# Sheet1.net
KiCad netlist of a schematic drawn in Altium Designer
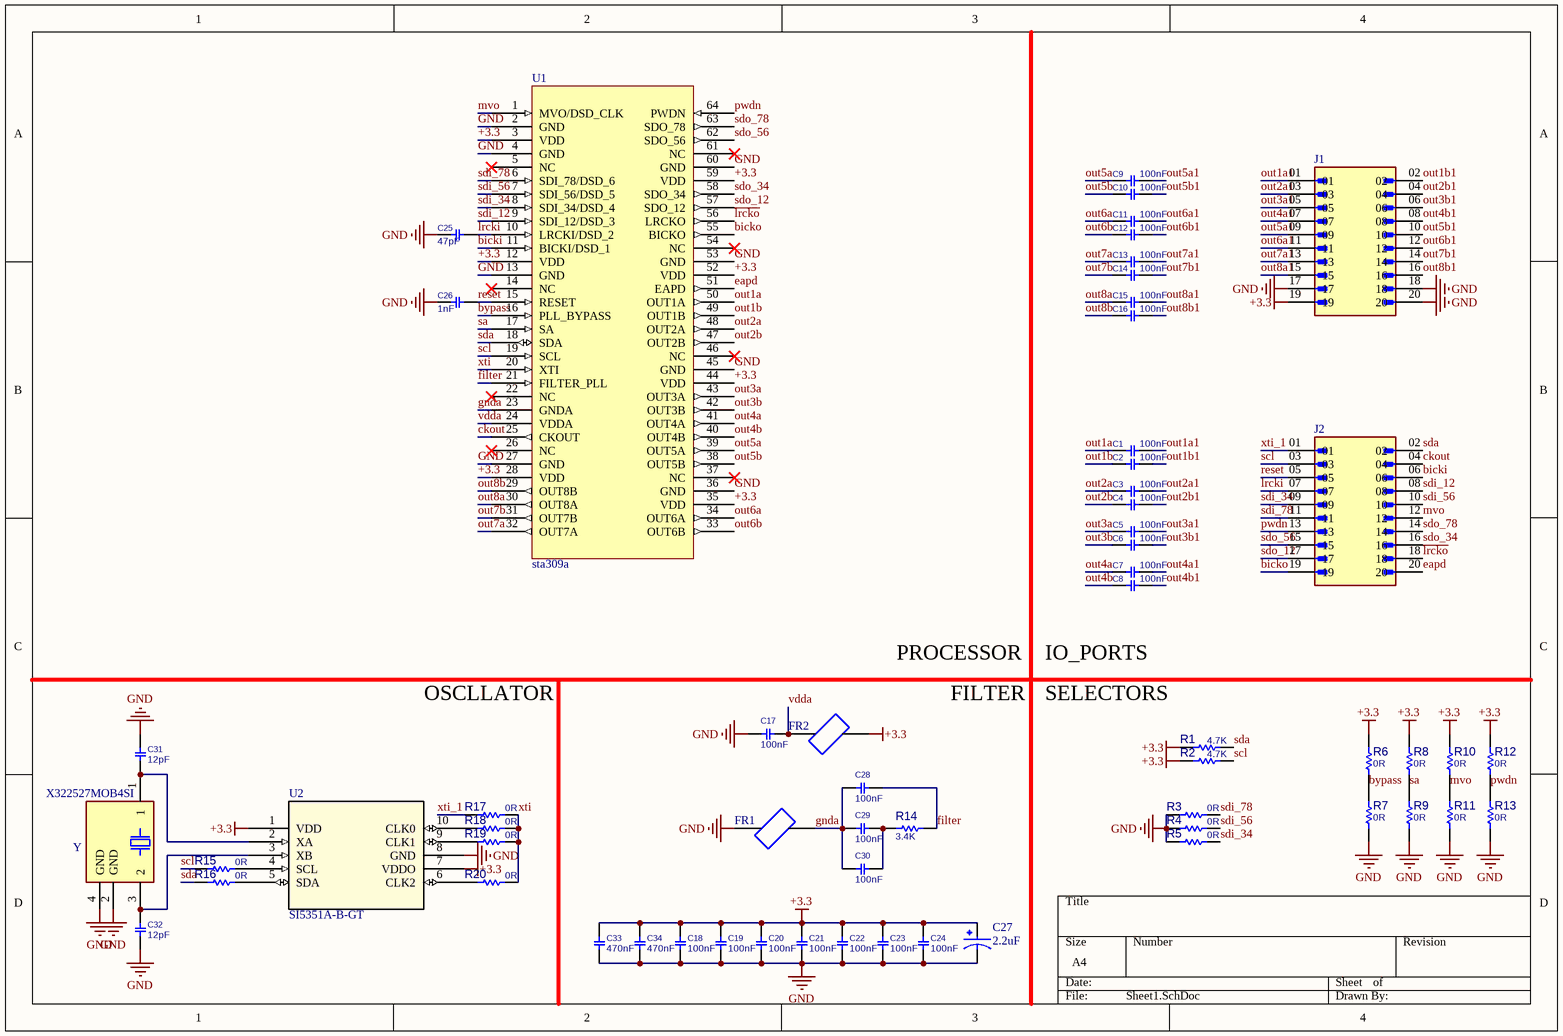
[diagram p0: Sheet1.SchDoc]

(export (version "E")
  (design (tool "Eeschema 10.0.6"))
  (components
    (comp (ref "C1")
      (value "100nF")
      (footprint "C0603")
      (description "CAP, MLCC")
      (fields (field (name "MANF_P#") "MANF_PART#"))
      (libsource (lib "receive") (part "CAP_SMD_MLCC_0603_1"))
    )
    (comp (ref "C2")
      (value "100nF")
      (footprint "C0603")
      (description "CAP, MLCC")
      (fields (field (name "MANF_P#") "MANF_PART#"))
      (libsource (lib "receive") (part "CAP_SMD_MLCC_0603_1"))
    )
    (comp (ref "C3")
      (value "100nF")
      (footprint "C0603")
      (description "CAP, MLCC")
      (fields (field (name "MANF_P#") "MANF_PART#"))
      (libsource (lib "receive") (part "CAP_SMD_MLCC_0603_1"))
    )
    (comp (ref "C4")
      (value "100nF")
      (footprint "C0603")
      (description "CAP, MLCC")
      (fields (field (name "MANF_P#") "MANF_PART#"))
      (libsource (lib "receive") (part "CAP_SMD_MLCC_0603_1"))
    )
    (comp (ref "C5")
      (value "100nF")
      (footprint "C0603")
      (description "CAP, MLCC")
      (fields (field (name "MANF_P#") "MANF_PART#"))
      (libsource (lib "receive") (part "CAP_SMD_MLCC_0603_1"))
    )
    (comp (ref "C6")
      (value "100nF")
      (footprint "C0603")
      (description "CAP, MLCC")
      (fields (field (name "MANF_P#") "MANF_PART#"))
      (libsource (lib "receive") (part "CAP_SMD_MLCC_0603_1"))
    )
    (comp (ref "C7")
      (value "100nF")
      (footprint "C0603")
      (description "CAP, MLCC")
      (fields (field (name "MANF_P#") "MANF_PART#"))
      (libsource (lib "receive") (part "CAP_SMD_MLCC_0603_1"))
    )
    (comp (ref "C8")
      (value "100nF")
      (footprint "C0603")
      (description "CAP, MLCC")
      (fields (field (name "MANF_P#") "MANF_PART#"))
      (libsource (lib "receive") (part "CAP_SMD_MLCC_0603_1"))
    )
    (comp (ref "C9")
      (value "100nF")
      (footprint "C0603")
      (description "CAP, MLCC")
      (fields (field (name "MANF_P#") "MANF_PART#"))
      (libsource (lib "receive") (part "CAP_SMD_MLCC_0603_1"))
    )
    (comp (ref "C10")
      (value "100nF")
      (footprint "C0603")
      (description "CAP, MLCC")
      (fields (field (name "MANF_P#") "MANF_PART#"))
      (libsource (lib "receive") (part "CAP_SMD_MLCC_0603_1"))
    )
    (comp (ref "C11")
      (value "100nF")
      (footprint "C0603")
      (description "CAP, MLCC")
      (fields (field (name "MANF_P#") "MANF_PART#"))
      (libsource (lib "receive") (part "CAP_SMD_MLCC_0603_1"))
    )
    (comp (ref "C12")
      (value "100nF")
      (footprint "C0603")
      (description "CAP, MLCC")
      (fields (field (name "MANF_P#") "MANF_PART#"))
      (libsource (lib "receive") (part "CAP_SMD_MLCC_0603_1"))
    )
    (comp (ref "C13")
      (value "100nF")
      (footprint "C0603")
      (description "CAP, MLCC")
      (fields (field (name "MANF_P#") "MANF_PART#"))
      (libsource (lib "receive") (part "CAP_SMD_MLCC_0603_1"))
    )
    (comp (ref "C14")
      (value "100nF")
      (footprint "C0603")
      (description "CAP, MLCC")
      (fields (field (name "MANF_P#") "MANF_PART#"))
      (libsource (lib "receive") (part "CAP_SMD_MLCC_0603_1"))
    )
    (comp (ref "C15")
      (value "100nF")
      (footprint "C0603")
      (description "CAP, MLCC")
      (fields (field (name "MANF_P#") "MANF_PART#"))
      (libsource (lib "receive") (part "CAP_SMD_MLCC_0603_1"))
    )
    (comp (ref "C16")
      (value "100nF")
      (footprint "C0603")
      (description "CAP, MLCC")
      (fields (field (name "MANF_P#") "MANF_PART#"))
      (libsource (lib "receive") (part "CAP_SMD_MLCC_0603_1"))
    )
    (comp (ref "C17")
      (value "100nF")
      (footprint "C0603")
      (description "CAP, MLCC")
      (fields (field (name "MANF_P#") "MANF_PART#"))
      (libsource (lib "receive") (part "CAP_SMD_MLCC_0603_1"))
    )
    (comp (ref "C18")
      (value "100nF")
      (footprint "C0603")
      (description "CAP, MLCC")
      (fields (field (name "MANF_P#") "MANF_PART#"))
      (libsource (lib "receive") (part "CAP_SMD_MLCC_0603_1"))
    )
    (comp (ref "C19")
      (value "100nF")
      (footprint "C0603")
      (description "CAP, MLCC")
      (fields (field (name "MANF_P#") "MANF_PART#"))
      (libsource (lib "receive") (part "CAP_SMD_MLCC_0603_1"))
    )
    (comp (ref "C20")
      (value "100nF")
      (footprint "C0603")
      (description "CAP, MLCC")
      (fields (field (name "MANF_P#") "MANF_PART#"))
      (libsource (lib "receive") (part "CAP_SMD_MLCC_0603_1"))
    )
    (comp (ref "C21")
      (value "100nF")
      (footprint "C0603")
      (description "CAP, MLCC")
      (fields (field (name "MANF_P#") "MANF_PART#"))
      (libsource (lib "receive") (part "CAP_SMD_MLCC_0603_1"))
    )
    (comp (ref "C22")
      (value "100nF")
      (footprint "C0603")
      (description "CAP, MLCC")
      (fields (field (name "MANF_P#") "MANF_PART#"))
      (libsource (lib "receive") (part "CAP_SMD_MLCC_0603_1"))
    )
    (comp (ref "C23")
      (value "100nF")
      (footprint "C0603")
      (description "CAP, MLCC")
      (fields (field (name "MANF_P#") "MANF_PART#"))
      (libsource (lib "receive") (part "CAP_SMD_MLCC_0603_1"))
    )
    (comp (ref "C24")
      (value "100nF")
      (footprint "C0603")
      (description "CAP, MLCC")
      (fields (field (name "MANF_P#") "MANF_PART#"))
      (libsource (lib "receive") (part "CAP_SMD_MLCC_0603_1"))
    )
    (comp (ref "C25")
      (value "47pF")
      (footprint "C0603")
      (description "CAP, MLCC")
      (fields (field (name "MANF_P#") "MANF_PART#"))
      (libsource (lib "receive") (part "CAP_SMD_MLCC_0603_1"))
    )
    (comp (ref "C26")
      (value "1nF")
      (footprint "C0603")
      (description "CAP, MLCC")
      (fields (field (name "MANF_P#") "MANF_PART#"))
      (libsource (lib "receive") (part "CAP_SMD_MLCC_0603_1"))
    )
    (comp (ref "C27")
      (value "2.2uF")
      (footprint "CAPMP3216X180N")
      (description "Capacitors Tantalum PCB 4.7uF SMD Tol 10% 10 VDC Case Size 3216 T491 Series ¦ KEMET T491A475K010AT")
      (fields (field (name "MF") "KEMET") (field (name "MP") "T491A475K010AT"))
      (libsource (lib "T491A475K010AT") (part "T491A475K010AT"))
    )
    (comp (ref "C28")
      (value "100nF")
      (footprint "C0603")
      (description "CAP, MLCC")
      (fields (field (name "MANF_P#") "MANF_PART#"))
      (libsource (lib "receive") (part "CAP_SMD_MLCC_0603_1"))
    )
    (comp (ref "C29")
      (value "100nF")
      (footprint "C0603")
      (description "CAP, MLCC")
      (fields (field (name "MANF_P#") "MANF_PART#"))
      (libsource (lib "receive") (part "CAP_SMD_MLCC_0603_1"))
    )
    (comp (ref "C30")
      (value "100nF")
      (footprint "C0603")
      (description "CAP, MLCC")
      (fields (field (name "MANF_P#") "MANF_PART#"))
      (libsource (lib "receive") (part "CAP_SMD_MLCC_0603_1"))
    )
    (comp (ref "C31")
      (value "12pF")
      (footprint "C0603")
      (description "CAP, MLCC")
      (fields (field (name "MANF_P#") "MANF_PART#"))
      (libsource (lib "receive") (part "CAP_SMD_MLCC_0603_1"))
    )
    (comp (ref "C32")
      (value "12pF")
      (footprint "C0603")
      (description "CAP, MLCC")
      (fields (field (name "MANF_P#") "MANF_PART#"))
      (libsource (lib "receive") (part "CAP_SMD_MLCC_0603_1"))
    )
    (comp (ref "C33")
      (value "470nF")
      (footprint "C0603")
      (description "CAP, MLCC")
      (fields (field (name "MANF_P#") "MANF_PART#"))
      (libsource (lib "receive") (part "CAP_SMD_MLCC_0603_1"))
    )
    (comp (ref "C34")
      (value "470nF")
      (footprint "C0603")
      (description "CAP, MLCC")
      (fields (field (name "MANF_P#") "MANF_PART#"))
      (libsource (lib "receive") (part "CAP_SMD_MLCC_0603_1"))
    )
    (comp (ref "FR1")
      (value "MI0805K400R-10")
      (footprint "FB_MI0805K400R-10")
      (description "40 Ohms @ 100MHz 1 Power Line Ferrite Bead 0805 (2012 Metric) 1.5A 50mOhm")
      (fields (field (name "MF") "Laird-Signal Integrity Products"))
      (libsource (lib "MI0805K400R-10") (part "MI0805K400R-10"))
    )
    (comp (ref "FR2")
      (value "MI0805K400R-10")
      (footprint "FB_MI0805K400R-10")
      (description "40 Ohms @ 100MHz 1 Power Line Ferrite Bead 0805 (2012 Metric) 1.5A 50mOhm")
      (fields (field (name "MF") "Laird-Signal Integrity Products"))
      (libsource (lib "MI0805K400R-10") (part "MI0805K400R-10"))
    )
    (comp (ref "J1")
      (value "VMHD-2x10-150-095-030")
      (footprint "VALCON_VMHD-2x10-150-095-030")
      (libsource (lib "VMHD-2x10-150-095-030") (part "VMHD-2x10-150-095-030"))
    )
    (comp (ref "J2")
      (value "VMHD-2x10-150-095-030")
      (footprint "VALCON_VMHD-2x10-150-095-030")
      (libsource (lib "VMHD-2x10-150-095-030") (part "VMHD-2x10-150-095-030"))
    )
    (comp (ref "R1")
      (value "4.7K")
      (footprint "R0603")
      (description "RESISTOR, SMD")
      (libsource (lib "receive") (part "RES_SMD_0603_1"))
    )
    (comp (ref "R2")
      (value "4.7K")
      (footprint "R0603")
      (description "RESISTOR, SMD")
      (libsource (lib "receive") (part "RES_SMD_0603_1"))
    )
    (comp (ref "R3")
      (value "0R")
      (footprint "R0603")
      (description "RESISTOR, SMD")
      (libsource (lib "receive") (part "RES_SMD_0603_1"))
    )
    (comp (ref "R4")
      (value "0R")
      (footprint "R0603")
      (description "RESISTOR, SMD")
      (libsource (lib "receive") (part "RES_SMD_0603_1"))
    )
    (comp (ref "R5")
      (value "0R")
      (footprint "R0603")
      (description "RESISTOR, SMD")
      (libsource (lib "receive") (part "RES_SMD_0603_1"))
    )
    (comp (ref "R6")
      (value "0R")
      (footprint "R0603")
      (description "RESISTOR, SMD")
      (libsource (lib "receive") (part "RES_SMD_0603_1"))
    )
    (comp (ref "R7")
      (value "0R")
      (footprint "R0603")
      (description "RESISTOR, SMD")
      (libsource (lib "receive") (part "RES_SMD_0603_1"))
    )
    (comp (ref "R8")
      (value "0R")
      (footprint "R0603")
      (description "RESISTOR, SMD")
      (libsource (lib "receive") (part "RES_SMD_0603_1"))
    )
    (comp (ref "R9")
      (value "0R")
      (footprint "R0603")
      (description "RESISTOR, SMD")
      (libsource (lib "receive") (part "RES_SMD_0603_1"))
    )
    (comp (ref "R10")
      (value "0R")
      (footprint "R0603")
      (description "RESISTOR, SMD")
      (libsource (lib "receive") (part "RES_SMD_0603_1"))
    )
    (comp (ref "R11")
      (value "0R")
      (footprint "R0603")
      (description "RESISTOR, SMD")
      (libsource (lib "receive") (part "RES_SMD_0603_1"))
    )
    (comp (ref "R12")
      (value "0R")
      (footprint "R0603")
      (description "RESISTOR, SMD")
      (libsource (lib "receive") (part "RES_SMD_0603_1"))
    )
    (comp (ref "R13")
      (value "0R")
      (footprint "R0603")
      (description "RESISTOR, SMD")
      (libsource (lib "receive") (part "RES_SMD_0603_1"))
    )
    (comp (ref "R14")
      (value "3.4K")
      (footprint "R0603")
      (description "RESISTOR, SMD")
      (libsource (lib "receive") (part "RES_SMD_0603_1"))
    )
    (comp (ref "R15")
      (value "0R")
      (footprint "R0603")
      (description "RESISTOR, SMD")
      (libsource (lib "receive") (part "RES_SMD_0603_1"))
    )
    (comp (ref "R16")
      (value "0R")
      (footprint "R0603")
      (description "RESISTOR, SMD")
      (libsource (lib "receive") (part "RES_SMD_0603_1"))
    )
    (comp (ref "R17")
      (value "0R")
      (footprint "R0603")
      (description "RESISTOR, SMD")
      (libsource (lib "receive") (part "RES_SMD_0603_1"))
    )
    (comp (ref "R18")
      (value "0R")
      (footprint "R0603")
      (description "RESISTOR, SMD")
      (libsource (lib "receive") (part "RES_SMD_0603_1"))
    )
    (comp (ref "R19")
      (value "0R")
      (footprint "R0603")
      (description "RESISTOR, SMD")
      (libsource (lib "receive") (part "RES_SMD_0603_1"))
    )
    (comp (ref "R20")
      (value "0R")
      (footprint "R0603")
      (description "RESISTOR, SMD")
      (libsource (lib "receive") (part "RES_SMD_0603_1"))
    )
    (comp (ref "U1")
      (value "sta309a")
      (footprint "QFP50P1200X1200X120-64N")
      (libsource (lib "sta309a") (part "sta309a"))
    )
    (comp (ref "U2")
      (value "SI5351A-B-GT")
      (footprint "10MSOP_3X3_SIL")
      (description "No Description Available")
      (fields (field (name "COPYRIGHT") "Copyright (C) 2025 Ultra Librarian. All rights reserved."))
      (libsource (lib "SI5351A-B-GT") (part "SI5351A-B-GT"))
    )
    (comp (ref "Y")
      (value "X322527MOB4SI")
      (footprint "XTAL_TSX-3225_16.0000MF18X-AC3")
      (description "16 MHz Â±10ppm Crystal 18pF 60 Ohms 4-SMD, No Lead")
      (fields (field (name "MF") "EPSON") (field (name "MP") "TSX-3225 16.0000MF18X-AC3"))
      (libsource (lib "TSX-3225_16.0000MF18X-AC3") (part "TSX-3225_16.0000MF18X-AC3"))
    )
  )
  (nets
    (net (code "1") (name "+3.3") (class "Default")
      (node (ref "C18") (pin "2") (pinfunction "2_2") (pintype "passive"))
      (node (ref "C19") (pin "2") (pinfunction "2_2") (pintype "passive"))
      (node (ref "C20") (pin "2") (pinfunction "2_2") (pintype "passive"))
      (node (ref "C21") (pin "2") (pinfunction "2_2") (pintype "passive"))
      (node (ref "C22") (pin "2") (pinfunction "2_2") (pintype "passive"))
      (node (ref "C23") (pin "2") (pinfunction "2_2") (pintype "passive"))
      (node (ref "C24") (pin "2") (pinfunction "2_2") (pintype "passive"))
      (node (ref "C27") (pin "1") (pinfunction "1_1") (pintype "passive"))
      (node (ref "C33") (pin "2") (pinfunction "2_2") (pintype "passive"))
      (node (ref "C34") (pin "2") (pinfunction "2_2") (pintype "passive"))
      (node (ref "FR2") (pin "1") (pinfunction "1_1") (pintype "passive"))
      (node (ref "J1") (pin "19") (pinfunction "19_19") (pintype "passive"))
      (node (ref "R1") (pin "1") (pinfunction "1_1") (pintype "passive"))
      (node (ref "R10") (pin "1") (pinfunction "1_1") (pintype "passive"))
      (node (ref "R12") (pin "1") (pinfunction "1_1") (pintype "passive"))
      (node (ref "R2") (pin "1") (pinfunction "1_1") (pintype "passive"))
      (node (ref "R6") (pin "1") (pinfunction "1_1") (pintype "passive"))
      (node (ref "R8") (pin "1") (pinfunction "1_1") (pintype "passive"))
      (node (ref "U1") (pin "12") (pinfunction "VDD_12") (pintype "power_in"))
      (node (ref "U1") (pin "28") (pinfunction "VDD_28") (pintype "power_in"))
      (node (ref "U1") (pin "3") (pinfunction "VDD_3") (pintype "power_in"))
      (node (ref "U1") (pin "35") (pinfunction "VDD_35") (pintype "power_in"))
      (node (ref "U1") (pin "44") (pinfunction "VDD_44") (pintype "power_in"))
      (node (ref "U1") (pin "52") (pinfunction "VDD_52") (pintype "power_in"))
      (node (ref "U1") (pin "59") (pinfunction "VDD_59") (pintype "power_in"))
      (node (ref "U2") (pin "1") (pinfunction "VDD_1") (pintype "power_in"))
      (node (ref "U2") (pin "7") (pinfunction "VDDO_7") (pintype "power_in"))
    )
    (net (code "2") (name "/bicki") (class "Default")
      (node (ref "J2") (pin "06") (pinfunction "06_06") (pintype "passive"))
      (node (ref "U1") (pin "11") (pinfunction "BICKI/DSD_1_11") (pintype "input"))
    )
    (net (code "3") (name "/bicko") (class "Default")
      (node (ref "J2") (pin "19") (pinfunction "19_19") (pintype "passive"))
      (node (ref "U1") (pin "55") (pinfunction "BICKO_55") (pintype "output"))
    )
    (net (code "4") (name "/bypass") (class "Default")
      (node (ref "R6") (pin "2") (pinfunction "2_2") (pintype "passive"))
      (node (ref "R7") (pin "2") (pinfunction "2_2") (pintype "passive"))
      (node (ref "U1") (pin "16") (pinfunction "PLL_BYPASS_16") (pintype "input"))
    )
    (net (code "5") (name "/ckout") (class "Default")
      (node (ref "J2") (pin "04") (pinfunction "04_04") (pintype "passive"))
      (node (ref "U1") (pin "25") (pinfunction "CKOUT_25") (pintype "output"))
    )
    (net (code "6") (name "/eapd") (class "Default")
      (node (ref "J2") (pin "20") (pinfunction "20_20") (pintype "passive"))
      (node (ref "U1") (pin "51") (pinfunction "EAPD_51") (pintype "output"))
    )
    (net (code "7") (name "/filter") (class "Default")
      (node (ref "C28") (pin "1") (pinfunction "1_1") (pintype "passive"))
      (node (ref "R14") (pin "2") (pinfunction "2_2") (pintype "passive"))
      (node (ref "U1") (pin "21") (pinfunction "FILTER_PLL_21") (pintype "input"))
    )
    (net (code "8") (name "/gnda") (class "Default")
      (node (ref "C28") (pin "2") (pinfunction "2_2") (pintype "passive"))
      (node (ref "C29") (pin "2") (pinfunction "2_2") (pintype "passive"))
      (node (ref "C30") (pin "2") (pinfunction "2_2") (pintype "passive"))
      (node (ref "FR1") (pin "2") (pinfunction "2_2") (pintype "passive"))
      (node (ref "U1") (pin "23") (pinfunction "GNDA_23") (pintype "power_in"))
    )
    (net (code "9") (name "/lrcki") (class "Default")
      (node (ref "C25") (pin "1") (pinfunction "1_1") (pintype "passive"))
      (node (ref "J2") (pin "07") (pinfunction "07_07") (pintype "passive"))
      (node (ref "U1") (pin "10") (pinfunction "LRCKI/DSD_2_10") (pintype "input"))
    )
    (net (code "10") (name "/lrcko") (class "Default")
      (node (ref "J2") (pin "18") (pinfunction "18_18") (pintype "passive"))
      (node (ref "U1") (pin "56") (pinfunction "LRCKO_56") (pintype "output"))
    )
    (net (code "11") (name "/mvo") (class "Default")
      (node (ref "J2") (pin "12") (pinfunction "12_12") (pintype "passive"))
      (node (ref "R10") (pin "2") (pinfunction "2_2") (pintype "passive"))
      (node (ref "R11") (pin "2") (pinfunction "2_2") (pintype "passive"))
      (node (ref "U1") (pin "1") (pinfunction "MVO/DSD_CLK_1") (pintype "input"))
    )
    (net (code "12") (name "/out1a") (class "Default")
      (node (ref "C1") (pin "1") (pinfunction "1_1") (pintype "passive"))
      (node (ref "U1") (pin "50") (pinfunction "OUT1A_50") (pintype "output"))
    )
    (net (code "13") (name "/out1a1") (class "Default")
      (node (ref "C1") (pin "2") (pinfunction "2_2") (pintype "passive"))
      (node (ref "J1") (pin "01") (pinfunction "01_01") (pintype "passive"))
    )
    (net (code "14") (name "/out1b") (class "Default")
      (node (ref "C2") (pin "1") (pinfunction "1_1") (pintype "passive"))
      (node (ref "U1") (pin "49") (pinfunction "OUT1B_49") (pintype "output"))
    )
    (net (code "15") (name "/out1b1") (class "Default")
      (node (ref "C2") (pin "2") (pinfunction "2_2") (pintype "passive"))
      (node (ref "J1") (pin "02") (pinfunction "02_02") (pintype "passive"))
    )
    (net (code "16") (name "/out2a") (class "Default")
      (node (ref "C3") (pin "1") (pinfunction "1_1") (pintype "passive"))
      (node (ref "U1") (pin "48") (pinfunction "OUT2A_48") (pintype "output"))
    )
    (net (code "17") (name "/out2a1") (class "Default")
      (node (ref "C3") (pin "2") (pinfunction "2_2") (pintype "passive"))
      (node (ref "J1") (pin "03") (pinfunction "03_03") (pintype "passive"))
    )
    (net (code "18") (name "/out2b") (class "Default")
      (node (ref "C4") (pin "1") (pinfunction "1_1") (pintype "passive"))
      (node (ref "U1") (pin "47") (pinfunction "OUT2B_47") (pintype "output"))
    )
    (net (code "19") (name "/out2b1") (class "Default")
      (node (ref "C4") (pin "2") (pinfunction "2_2") (pintype "passive"))
      (node (ref "J1") (pin "04") (pinfunction "04_04") (pintype "passive"))
    )
    (net (code "20") (name "/out3a") (class "Default")
      (node (ref "C5") (pin "1") (pinfunction "1_1") (pintype "passive"))
      (node (ref "U1") (pin "43") (pinfunction "OUT3A_43") (pintype "output"))
    )
    (net (code "21") (name "/out3a1") (class "Default")
      (node (ref "C5") (pin "2") (pinfunction "2_2") (pintype "passive"))
      (node (ref "J1") (pin "05") (pinfunction "05_05") (pintype "passive"))
    )
    (net (code "22") (name "/out3b") (class "Default")
      (node (ref "C6") (pin "1") (pinfunction "1_1") (pintype "passive"))
      (node (ref "U1") (pin "42") (pinfunction "OUT3B_42") (pintype "output"))
    )
    (net (code "23") (name "/out3b1") (class "Default")
      (node (ref "C6") (pin "2") (pinfunction "2_2") (pintype "passive"))
      (node (ref "J1") (pin "06") (pinfunction "06_06") (pintype "passive"))
    )
    (net (code "24") (name "/out4a") (class "Default")
      (node (ref "C7") (pin "1") (pinfunction "1_1") (pintype "passive"))
      (node (ref "U1") (pin "41") (pinfunction "OUT4A_41") (pintype "output"))
    )
    (net (code "25") (name "/out4a1") (class "Default")
      (node (ref "C7") (pin "2") (pinfunction "2_2") (pintype "passive"))
      (node (ref "J1") (pin "07") (pinfunction "07_07") (pintype "passive"))
    )
    (net (code "26") (name "/out4b") (class "Default")
      (node (ref "C8") (pin "1") (pinfunction "1_1") (pintype "passive"))
      (node (ref "U1") (pin "40") (pinfunction "OUT4B_40") (pintype "output"))
    )
    (net (code "27") (name "/out4b1") (class "Default")
      (node (ref "C8") (pin "2") (pinfunction "2_2") (pintype "passive"))
      (node (ref "J1") (pin "08") (pinfunction "08_08") (pintype "passive"))
    )
    (net (code "28") (name "/out5a") (class "Default")
      (node (ref "C9") (pin "1") (pinfunction "1_1") (pintype "passive"))
      (node (ref "U1") (pin "39") (pinfunction "OUT5A_39") (pintype "output"))
    )
    (net (code "29") (name "/out5a1") (class "Default")
      (node (ref "C9") (pin "2") (pinfunction "2_2") (pintype "passive"))
      (node (ref "J1") (pin "09") (pinfunction "09_09") (pintype "passive"))
    )
    (net (code "30") (name "/out5b") (class "Default")
      (node (ref "C10") (pin "1") (pinfunction "1_1") (pintype "passive"))
      (node (ref "U1") (pin "38") (pinfunction "OUT5B_38") (pintype "output"))
    )
    (net (code "31") (name "/out5b1") (class "Default")
      (node (ref "C10") (pin "2") (pinfunction "2_2") (pintype "passive"))
      (node (ref "J1") (pin "10") (pinfunction "10_10") (pintype "passive"))
    )
    (net (code "32") (name "/out6a") (class "Default")
      (node (ref "C11") (pin "1") (pinfunction "1_1") (pintype "passive"))
      (node (ref "U1") (pin "34") (pinfunction "OUT6A_34") (pintype "output"))
    )
    (net (code "33") (name "/out6a1") (class "Default")
      (node (ref "C11") (pin "2") (pinfunction "2_2") (pintype "passive"))
      (node (ref "J1") (pin "11") (pinfunction "11_11") (pintype "passive"))
    )
    (net (code "34") (name "/out6b") (class "Default")
      (node (ref "C12") (pin "1") (pinfunction "1_1") (pintype "passive"))
      (node (ref "U1") (pin "33") (pinfunction "OUT6B_33") (pintype "output"))
    )
    (net (code "35") (name "/out6b1") (class "Default")
      (node (ref "C12") (pin "2") (pinfunction "2_2") (pintype "passive"))
      (node (ref "J1") (pin "12") (pinfunction "12_12") (pintype "passive"))
    )
    (net (code "36") (name "/out7a") (class "Default")
      (node (ref "C13") (pin "1") (pinfunction "1_1") (pintype "passive"))
      (node (ref "U1") (pin "32") (pinfunction "OUT7A_32") (pintype "output"))
    )
    (net (code "37") (name "/out7a1") (class "Default")
      (node (ref "C13") (pin "2") (pinfunction "2_2") (pintype "passive"))
      (node (ref "J1") (pin "13") (pinfunction "13_13") (pintype "passive"))
    )
    (net (code "38") (name "/out7b") (class "Default")
      (node (ref "C14") (pin "1") (pinfunction "1_1") (pintype "passive"))
      (node (ref "U1") (pin "31") (pinfunction "OUT7B_31") (pintype "output"))
    )
    (net (code "39") (name "/out7b1") (class "Default")
      (node (ref "C14") (pin "2") (pinfunction "2_2") (pintype "passive"))
      (node (ref "J1") (pin "14") (pinfunction "14_14") (pintype "passive"))
    )
    (net (code "40") (name "/out8a") (class "Default")
      (node (ref "C15") (pin "1") (pinfunction "1_1") (pintype "passive"))
      (node (ref "U1") (pin "30") (pinfunction "OUT8A_30") (pintype "output"))
    )
    (net (code "41") (name "/out8a1") (class "Default")
      (node (ref "C15") (pin "2") (pinfunction "2_2") (pintype "passive"))
      (node (ref "J1") (pin "15") (pinfunction "15_15") (pintype "passive"))
    )
    (net (code "42") (name "/out8b") (class "Default")
      (node (ref "C16") (pin "1") (pinfunction "1_1") (pintype "passive"))
      (node (ref "U1") (pin "29") (pinfunction "OUT8B_29") (pintype "output"))
    )
    (net (code "43") (name "/out8b1") (class "Default")
      (node (ref "C16") (pin "2") (pinfunction "2_2") (pintype "passive"))
      (node (ref "J1") (pin "16") (pinfunction "16_16") (pintype "passive"))
    )
    (net (code "44") (name "/pwdn") (class "Default")
      (node (ref "J2") (pin "13") (pinfunction "13_13") (pintype "passive"))
      (node (ref "R12") (pin "2") (pinfunction "2_2") (pintype "passive"))
      (node (ref "R13") (pin "2") (pinfunction "2_2") (pintype "passive"))
      (node (ref "U1") (pin "64") (pinfunction "PWDN_64") (pintype "input"))
    )
    (net (code "45") (name "/reset") (class "Default")
      (node (ref "C26") (pin "1") (pinfunction "1_1") (pintype "passive"))
      (node (ref "J2") (pin "05") (pinfunction "05_05") (pintype "passive"))
      (node (ref "U1") (pin "15") (pinfunction "RESET_15") (pintype "input"))
    )
    (net (code "46") (name "/sa") (class "Default")
      (node (ref "R8") (pin "2") (pinfunction "2_2") (pintype "passive"))
      (node (ref "R9") (pin "2") (pinfunction "2_2") (pintype "passive"))
      (node (ref "U1") (pin "17") (pinfunction "SA_17") (pintype "input"))
    )
    (net (code "47") (name "/scl") (class "Default")
      (node (ref "J2") (pin "03") (pinfunction "03_03") (pintype "passive"))
      (node (ref "R15") (pin "1") (pinfunction "1_1") (pintype "passive"))
      (node (ref "R2") (pin "2") (pinfunction "2_2") (pintype "passive"))
      (node (ref "U1") (pin "19") (pinfunction "SCL_19") (pintype "input"))
    )
    (net (code "48") (name "/sda") (class "Default")
      (node (ref "J2") (pin "02") (pinfunction "02_02") (pintype "passive"))
      (node (ref "R1") (pin "2") (pinfunction "2_2") (pintype "passive"))
      (node (ref "R16") (pin "1") (pinfunction "1_1") (pintype "passive"))
      (node (ref "U1") (pin "18") (pinfunction "SDA_18") (pintype "bidirectional"))
    )
    (net (code "49") (name "/sdi_12") (class "Default")
      (node (ref "J2") (pin "08") (pinfunction "08_08") (pintype "passive"))
      (node (ref "U1") (pin "9") (pinfunction "SDI_12/DSD_3_9") (pintype "input"))
    )
    (net (code "50") (name "/sdi_34") (class "Default")
      (node (ref "J2") (pin "09") (pinfunction "09_09") (pintype "passive"))
      (node (ref "R5") (pin "2") (pinfunction "2_2") (pintype "passive"))
      (node (ref "U1") (pin "8") (pinfunction "SDI_34/DSD_4_8") (pintype "input"))
    )
    (net (code "51") (name "/sdi_56") (class "Default")
      (node (ref "J2") (pin "10") (pinfunction "10_10") (pintype "passive"))
      (node (ref "R4") (pin "2") (pinfunction "2_2") (pintype "passive"))
      (node (ref "U1") (pin "7") (pinfunction "SDI_56/DSD_5_7") (pintype "input"))
    )
    (net (code "52") (name "/sdi_78") (class "Default")
      (node (ref "J2") (pin "11") (pinfunction "11_11") (pintype "passive"))
      (node (ref "R3") (pin "2") (pinfunction "2_2") (pintype "passive"))
      (node (ref "U1") (pin "6") (pinfunction "SDI_78/DSD_6_6") (pintype "input"))
    )
    (net (code "53") (name "/sdo_12") (class "Default")
      (node (ref "J2") (pin "17") (pinfunction "17_17") (pintype "passive"))
      (node (ref "U1") (pin "57") (pinfunction "SDO_12_57") (pintype "output"))
    )
    (net (code "54") (name "/sdo_34") (class "Default")
      (node (ref "J2") (pin "16") (pinfunction "16_16") (pintype "passive"))
      (node (ref "U1") (pin "58") (pinfunction "SDO_34_58") (pintype "output"))
    )
    (net (code "55") (name "/sdo_56") (class "Default")
      (node (ref "J2") (pin "15") (pinfunction "15_15") (pintype "passive"))
      (node (ref "U1") (pin "62") (pinfunction "SDO_56_62") (pintype "output"))
    )
    (net (code "56") (name "/sdo_78") (class "Default")
      (node (ref "J2") (pin "14") (pinfunction "14_14") (pintype "passive"))
      (node (ref "U1") (pin "63") (pinfunction "SDO_78_63") (pintype "output"))
    )
    (net (code "57") (name "/vdda") (class "Default")
      (node (ref "C17") (pin "2") (pinfunction "2_2") (pintype "passive"))
      (node (ref "FR2") (pin "2") (pinfunction "2_2") (pintype "passive"))
      (node (ref "U1") (pin "24") (pinfunction "VDDA_24") (pintype "power_in"))
    )
    (net (code "58") (name "/xti") (class "Default")
      (node (ref "R17") (pin "2") (pinfunction "2_2") (pintype "passive"))
      (node (ref "R18") (pin "2") (pinfunction "2_2") (pintype "passive"))
      (node (ref "R19") (pin "2") (pinfunction "2_2") (pintype "passive"))
      (node (ref "R20") (pin "2") (pinfunction "2_2") (pintype "passive"))
      (node (ref "U1") (pin "20") (pinfunction "XTI_20") (pintype "input"))
    )
    (net (code "59") (name "/xti_1") (class "Default")
      (node (ref "J2") (pin "01") (pinfunction "01_01") (pintype "passive"))
      (node (ref "R17") (pin "1") (pinfunction "1_1") (pintype "passive"))
    )
    (net (code "60") (name "GND") (class "Default")
      (node (ref "C17") (pin "1") (pinfunction "1_1") (pintype "passive"))
      (node (ref "C18") (pin "1") (pinfunction "1_1") (pintype "passive"))
      (node (ref "C19") (pin "1") (pinfunction "1_1") (pintype "passive"))
      (node (ref "C20") (pin "1") (pinfunction "1_1") (pintype "passive"))
      (node (ref "C21") (pin "1") (pinfunction "1_1") (pintype "passive"))
      (node (ref "C22") (pin "1") (pinfunction "1_1") (pintype "passive"))
      (node (ref "C23") (pin "1") (pinfunction "1_1") (pintype "passive"))
      (node (ref "C24") (pin "1") (pinfunction "1_1") (pintype "passive"))
      (node (ref "C25") (pin "2") (pinfunction "2_2") (pintype "passive"))
      (node (ref "C26") (pin "2") (pinfunction "2_2") (pintype "passive"))
      (node (ref "C27") (pin "2") (pinfunction "2_2") (pintype "passive"))
      (node (ref "C31") (pin "2") (pinfunction "2_2") (pintype "passive"))
      (node (ref "C32") (pin "2") (pinfunction "2_2") (pintype "passive"))
      (node (ref "C33") (pin "1") (pinfunction "1_1") (pintype "passive"))
      (node (ref "C34") (pin "1") (pinfunction "1_1") (pintype "passive"))
      (node (ref "FR1") (pin "1") (pinfunction "1_1") (pintype "passive"))
      (node (ref "J1") (pin "17") (pinfunction "17_17") (pintype "passive"))
      (node (ref "J1") (pin "18") (pinfunction "18_18") (pintype "passive"))
      (node (ref "J1") (pin "20") (pinfunction "20_20") (pintype "passive"))
      (node (ref "R11") (pin "1") (pinfunction "1_1") (pintype "passive"))
      (node (ref "R13") (pin "1") (pinfunction "1_1") (pintype "passive"))
      (node (ref "R3") (pin "1") (pinfunction "1_1") (pintype "passive"))
      (node (ref "R4") (pin "1") (pinfunction "1_1") (pintype "passive"))
      (node (ref "R5") (pin "1") (pinfunction "1_1") (pintype "passive"))
      (node (ref "R7") (pin "1") (pinfunction "1_1") (pintype "passive"))
      (node (ref "R9") (pin "1") (pinfunction "1_1") (pintype "passive"))
      (node (ref "U1") (pin "13") (pinfunction "GND_13") (pintype "power_in"))
      (node (ref "U1") (pin "2") (pinfunction "GND_2") (pintype "power_in"))
      (node (ref "U1") (pin "27") (pinfunction "GND_27") (pintype "power_in"))
      (node (ref "U1") (pin "36") (pinfunction "GND_36") (pintype "power_in"))
      (node (ref "U1") (pin "4") (pinfunction "GND_4") (pintype "power_in"))
      (node (ref "U1") (pin "45") (pinfunction "GND_45") (pintype "power_in"))
      (node (ref "U1") (pin "53") (pinfunction "GND_53") (pintype "power_in"))
      (node (ref "U1") (pin "60") (pinfunction "GND_60") (pintype "power_in"))
      (node (ref "U2") (pin "8") (pinfunction "GND_8") (pintype "power_in"))
      (node (ref "Y") (pin "2") (pinfunction "GND_2") (pintype "power_in"))
      (node (ref "Y") (pin "4") (pinfunction "GND_4") (pintype "power_in"))
    )
    (net (code "61") (name "Net-(C29-Pad1)") (class "Default")
      (node (ref "C29") (pin "1") (pinfunction "1_1") (pintype "passive"))
      (node (ref "C30") (pin "1") (pinfunction "1_1") (pintype "passive"))
      (node (ref "R14") (pin "1") (pinfunction "1_1") (pintype "passive"))
    )
    (net (code "62") (name "Net-(U2-CLK0)") (class "Default")
      (node (ref "R18") (pin "1") (pinfunction "1_1") (pintype "passive"))
      (node (ref "U2") (pin "10") (pinfunction "CLK0_10") (pintype "bidirectional"))
    )
    (net (code "63") (name "Net-(U2-CLK1)") (class "Default")
      (node (ref "R19") (pin "1") (pinfunction "1_1") (pintype "passive"))
      (node (ref "U2") (pin "9") (pinfunction "CLK1_9") (pintype "bidirectional"))
    )
    (net (code "64") (name "Net-(U2-CLK2)") (class "Default")
      (node (ref "R20") (pin "1") (pinfunction "1_1") (pintype "passive"))
      (node (ref "U2") (pin "6") (pinfunction "CLK2_6") (pintype "bidirectional"))
    )
    (net (code "65") (name "Net-(U2-SCL)") (class "Default")
      (node (ref "R15") (pin "2") (pinfunction "2_2") (pintype "passive"))
      (node (ref "U2") (pin "4") (pinfunction "SCL_4") (pintype "input"))
    )
    (net (code "66") (name "Net-(U2-SDA)") (class "Default")
      (node (ref "R16") (pin "2") (pinfunction "2_2") (pintype "passive"))
      (node (ref "U2") (pin "5") (pinfunction "SDA_5") (pintype "bidirectional"))
    )
    (net (code "67") (name "Net-(U2-XA)") (class "Default")
      (node (ref "C31") (pin "1") (pinfunction "1_1") (pintype "passive"))
      (node (ref "U2") (pin "2") (pinfunction "XA_2") (pintype "input"))
      (node (ref "Y") (pin "1") (pinfunction "1_1") (pintype "passive"))
    )
    (net (code "68") (name "Net-(U2-XB)") (class "Default")
      (node (ref "C32") (pin "1") (pinfunction "1_1") (pintype "passive"))
      (node (ref "U2") (pin "3") (pinfunction "XB_3") (pintype "input"))
      (node (ref "Y") (pin "3") (pinfunction "2_3") (pintype "passive"))
    )
    (net (code "69") (name "unconnected-(U1-NC-Pad5)") (class "Default")
      (node (ref "U1") (pin "5") (pinfunction "NC_5") (pintype "passive+no_connect"))
    )
    (net (code "70") (name "unconnected-(U1-NC-Pad14)") (class "Default")
      (node (ref "U1") (pin "14") (pinfunction "NC_14") (pintype "passive+no_connect"))
    )
    (net (code "71") (name "unconnected-(U1-NC-Pad22)") (class "Default")
      (node (ref "U1") (pin "22") (pinfunction "NC_22") (pintype "passive+no_connect"))
    )
    (net (code "72") (name "unconnected-(U1-NC-Pad26)") (class "Default")
      (node (ref "U1") (pin "26") (pinfunction "NC_26") (pintype "passive+no_connect"))
    )
    (net (code "73") (name "unconnected-(U1-NC-Pad37)") (class "Default")
      (node (ref "U1") (pin "37") (pinfunction "NC_37") (pintype "passive+no_connect"))
    )
    (net (code "74") (name "unconnected-(U1-NC-Pad46)") (class "Default")
      (node (ref "U1") (pin "46") (pinfunction "NC_46") (pintype "passive+no_connect"))
    )
    (net (code "75") (name "unconnected-(U1-NC-Pad54)") (class "Default")
      (node (ref "U1") (pin "54") (pinfunction "NC_54") (pintype "passive+no_connect"))
    )
    (net (code "76") (name "unconnected-(U1-NC-Pad61)") (class "Default")
      (node (ref "U1") (pin "61") (pinfunction "NC_61") (pintype "passive+no_connect"))
    )
  )
)
